# saa1064.net
KiCad netlist of a schematic drawn in EAGLE
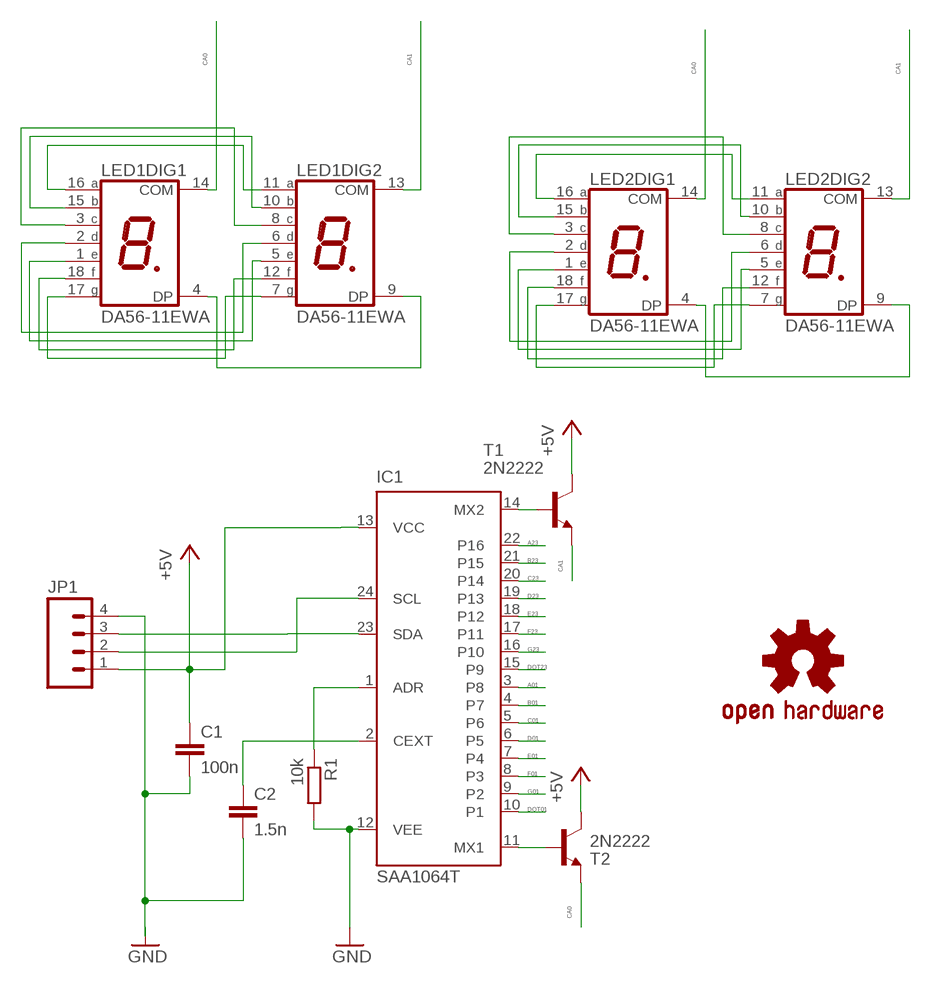
[diagram p0: schematic, sheet 1]

(export (version "E")
  (design (tool "Eeschema 10.0.6"))
  (components
    (comp (ref "C1")
      (value "100n")
      (footprint "eagle-import:C0805K")
      (libsource (lib "eagle-import") (part "C-EUC0805K"))
    )
    (comp (ref "C2")
      (value "1.5n")
      (footprint "eagle-import:C0805K")
      (libsource (lib "eagle-import") (part "C-EUC0805K"))
    )
    (comp (ref "IC1")
      (value "SAA1064T")
      (footprint "eagle-import:SO24")
      (fields (field (name "MPN") "SAA1064T/N2,118"))
      (libsource (lib "eagle-import") (part "SAA1064T"))
    )
    (comp (ref "JP1")
      (value "M04LONGPADS")
      (footprint "eagle-import:1X04_LONGPADS")
      (libsource (lib "eagle-import") (part "M04LONGPADS"))
    )
    (comp (ref "LED1")
      (value "DA56-11EWA")
      (footprint "eagle-import:DA56")
      (libsource (lib "eagle-import") (part "DA56-11EWA"))
    )
    (comp (ref "LED2")
      (value "DA56-11EWA")
      (footprint "eagle-import:DA56")
      (libsource (lib "eagle-import") (part "DA56-11EWA"))
    )
    (comp (ref "R1")
      (value "10k")
      (footprint "eagle-import:M0805")
      (libsource (lib "eagle-import") (part "R-EU_M0805"))
    )
    (comp (ref "T1")
      (value "2N2222")
      (footprint "eagle-import:TO92-EBC-OVAL")
      (libsource (lib "eagle-import") (part "2N2222"))
    )
    (comp (ref "T2")
      (value "2N2222")
      (footprint "eagle-import:TO92-EBC-OVAL")
      (libsource (lib "eagle-import") (part "2N2222"))
    )
    (comp (ref "U$1")
      (value "OSHW-LOGOS")
      (footprint "eagle-import:OSHW-LOGO-S")
      (libsource (lib "eagle-import") (part "OSHW-LOGOS"))
    )
  )
  (nets
    (net (code "1") (name "+5V") (class "Default")
      (node (ref "C1") (pin "1") (pinfunction "1_1") (pintype "passive"))
      (node (ref "IC1") (pin "13") (pinfunction "VCC_13") (pintype "power_in"))
      (node (ref "JP1") (pin "1") (pinfunction "1_1") (pintype "passive"))
      (node (ref "T1") (pin "C") (pinfunction "C_C") (pintype "passive"))
      (node (ref "T2") (pin "C") (pinfunction "C_C") (pintype "passive"))
    )
    (net (code "2") (name "/A01") (class "Default")
      (node (ref "IC1") (pin "3") (pinfunction "P8_3") (pintype "output"))
      (node (ref "LED1") (pin "11") (pinfunction "A_11") (pintype "passive"))
      (node (ref "LED1") (pin "16") (pinfunction "A_16") (pintype "passive"))
    )
    (net (code "3") (name "/A23") (class "Default")
      (node (ref "IC1") (pin "22") (pinfunction "P16_22") (pintype "output"))
      (node (ref "LED2") (pin "11") (pinfunction "A_11") (pintype "passive"))
      (node (ref "LED2") (pin "16") (pinfunction "A_16") (pintype "passive"))
    )
    (net (code "4") (name "/B01") (class "Default")
      (node (ref "IC1") (pin "4") (pinfunction "P7_4") (pintype "output"))
      (node (ref "LED1") (pin "10") (pinfunction "B_10") (pintype "passive"))
      (node (ref "LED1") (pin "15") (pinfunction "B_15") (pintype "passive"))
    )
    (net (code "5") (name "/B23") (class "Default")
      (node (ref "IC1") (pin "21") (pinfunction "P15_21") (pintype "output"))
      (node (ref "LED2") (pin "10") (pinfunction "B_10") (pintype "passive"))
      (node (ref "LED2") (pin "15") (pinfunction "B_15") (pintype "passive"))
    )
    (net (code "6") (name "/C01") (class "Default")
      (node (ref "IC1") (pin "5") (pinfunction "P6_5") (pintype "output"))
      (node (ref "LED1") (pin "3") (pinfunction "C_3") (pintype "passive"))
      (node (ref "LED1") (pin "8") (pinfunction "C_8") (pintype "passive"))
    )
    (net (code "7") (name "/C23") (class "Default")
      (node (ref "IC1") (pin "20") (pinfunction "P14_20") (pintype "output"))
      (node (ref "LED2") (pin "3") (pinfunction "C_3") (pintype "passive"))
      (node (ref "LED2") (pin "8") (pinfunction "C_8") (pintype "passive"))
    )
    (net (code "8") (name "/CA0") (class "Default")
      (node (ref "LED1") (pin "14") (pinfunction "COM_14") (pintype "passive"))
      (node (ref "LED2") (pin "14") (pinfunction "COM_14") (pintype "passive"))
      (node (ref "T2") (pin "E") (pinfunction "E_E") (pintype "passive"))
    )
    (net (code "9") (name "/CA1") (class "Default")
      (node (ref "LED1") (pin "13") (pinfunction "COM_13") (pintype "passive"))
      (node (ref "LED2") (pin "13") (pinfunction "COM_13") (pintype "passive"))
      (node (ref "T1") (pin "E") (pinfunction "E_E") (pintype "passive"))
    )
    (net (code "10") (name "/D01") (class "Default")
      (node (ref "IC1") (pin "6") (pinfunction "P5_6") (pintype "output"))
      (node (ref "LED1") (pin "2") (pinfunction "D_2") (pintype "passive"))
      (node (ref "LED1") (pin "6") (pinfunction "D_6") (pintype "passive"))
    )
    (net (code "11") (name "/D23") (class "Default")
      (node (ref "IC1") (pin "19") (pinfunction "P13_19") (pintype "output"))
      (node (ref "LED2") (pin "2") (pinfunction "D_2") (pintype "passive"))
      (node (ref "LED2") (pin "6") (pinfunction "D_6") (pintype "passive"))
    )
    (net (code "12") (name "/DOT01") (class "Default")
      (node (ref "IC1") (pin "10") (pinfunction "P1_10") (pintype "output"))
      (node (ref "LED1") (pin "4") (pinfunction "DP_4") (pintype "passive"))
      (node (ref "LED1") (pin "9") (pinfunction "DP_9") (pintype "passive"))
    )
    (net (code "13") (name "/DOT23") (class "Default")
      (node (ref "IC1") (pin "15") (pinfunction "P9_15") (pintype "output"))
      (node (ref "LED2") (pin "4") (pinfunction "DP_4") (pintype "passive"))
      (node (ref "LED2") (pin "9") (pinfunction "DP_9") (pintype "passive"))
    )
    (net (code "14") (name "/E01") (class "Default")
      (node (ref "IC1") (pin "7") (pinfunction "P4_7") (pintype "output"))
      (node (ref "LED1") (pin "1") (pinfunction "E_1") (pintype "passive"))
      (node (ref "LED1") (pin "5") (pinfunction "E_5") (pintype "passive"))
    )
    (net (code "15") (name "/E23") (class "Default")
      (node (ref "IC1") (pin "18") (pinfunction "P12_18") (pintype "output"))
      (node (ref "LED2") (pin "1") (pinfunction "E_1") (pintype "passive"))
      (node (ref "LED2") (pin "5") (pinfunction "E_5") (pintype "passive"))
    )
    (net (code "16") (name "/F01") (class "Default")
      (node (ref "IC1") (pin "8") (pinfunction "P3_8") (pintype "output"))
      (node (ref "LED1") (pin "12") (pinfunction "F_12") (pintype "passive"))
      (node (ref "LED1") (pin "18") (pinfunction "F_18") (pintype "passive"))
    )
    (net (code "17") (name "/F23") (class "Default")
      (node (ref "IC1") (pin "17") (pinfunction "P11_17") (pintype "output"))
      (node (ref "LED2") (pin "12") (pinfunction "F_12") (pintype "passive"))
      (node (ref "LED2") (pin "18") (pinfunction "F_18") (pintype "passive"))
    )
    (net (code "18") (name "/G01") (class "Default")
      (node (ref "IC1") (pin "9") (pinfunction "P2_9") (pintype "output"))
      (node (ref "LED1") (pin "17") (pinfunction "G_17") (pintype "passive"))
      (node (ref "LED1") (pin "7") (pinfunction "G_7") (pintype "passive"))
    )
    (net (code "19") (name "/G23") (class "Default")
      (node (ref "IC1") (pin "16") (pinfunction "P10_16") (pintype "output"))
      (node (ref "LED2") (pin "17") (pinfunction "G_17") (pintype "passive"))
      (node (ref "LED2") (pin "7") (pinfunction "G_7") (pintype "passive"))
    )
    (net (code "20") (name "GND") (class "Default")
      (node (ref "C1") (pin "2") (pinfunction "2_2") (pintype "passive"))
      (node (ref "C2") (pin "2") (pinfunction "2_2") (pintype "passive"))
      (node (ref "IC1") (pin "12") (pinfunction "VEE_12") (pintype "power_in"))
      (node (ref "JP1") (pin "4") (pinfunction "4_4") (pintype "passive"))
      (node (ref "R1") (pin "2") (pinfunction "2_2") (pintype "passive"))
    )
    (net (code "21") (name "Net-(IC1-ADR)") (class "Default")
      (node (ref "IC1") (pin "1") (pinfunction "ADR_1") (pintype "input"))
      (node (ref "R1") (pin "1") (pinfunction "1_1") (pintype "passive"))
    )
    (net (code "22") (name "Net-(IC1-CEXT)") (class "Default")
      (node (ref "C2") (pin "1") (pinfunction "1_1") (pintype "passive"))
      (node (ref "IC1") (pin "2") (pinfunction "CEXT_2") (pintype "input"))
    )
    (net (code "23") (name "Net-(IC1-MX1)") (class "Default")
      (node (ref "IC1") (pin "11") (pinfunction "MX1_11") (pintype "output"))
      (node (ref "T2") (pin "B") (pinfunction "B_B") (pintype "passive"))
    )
    (net (code "24") (name "Net-(IC1-MX2)") (class "Default")
      (node (ref "IC1") (pin "14") (pinfunction "MX2_14") (pintype "output"))
      (node (ref "T1") (pin "B") (pinfunction "B_B") (pintype "passive"))
    )
    (net (code "25") (name "Net-(IC1-SCL)") (class "Default")
      (node (ref "IC1") (pin "24") (pinfunction "SCL_24") (pintype "input"))
      (node (ref "JP1") (pin "2") (pinfunction "2_2") (pintype "passive"))
    )
    (net (code "26") (name "Net-(IC1-SDA)") (class "Default")
      (node (ref "IC1") (pin "23") (pinfunction "SDA_23") (pintype "input"))
      (node (ref "JP1") (pin "3") (pinfunction "3_3") (pintype "passive"))
    )
  )
)
